# motion_detect.net
KiCad netlist of a schematic drawn in EAGLE
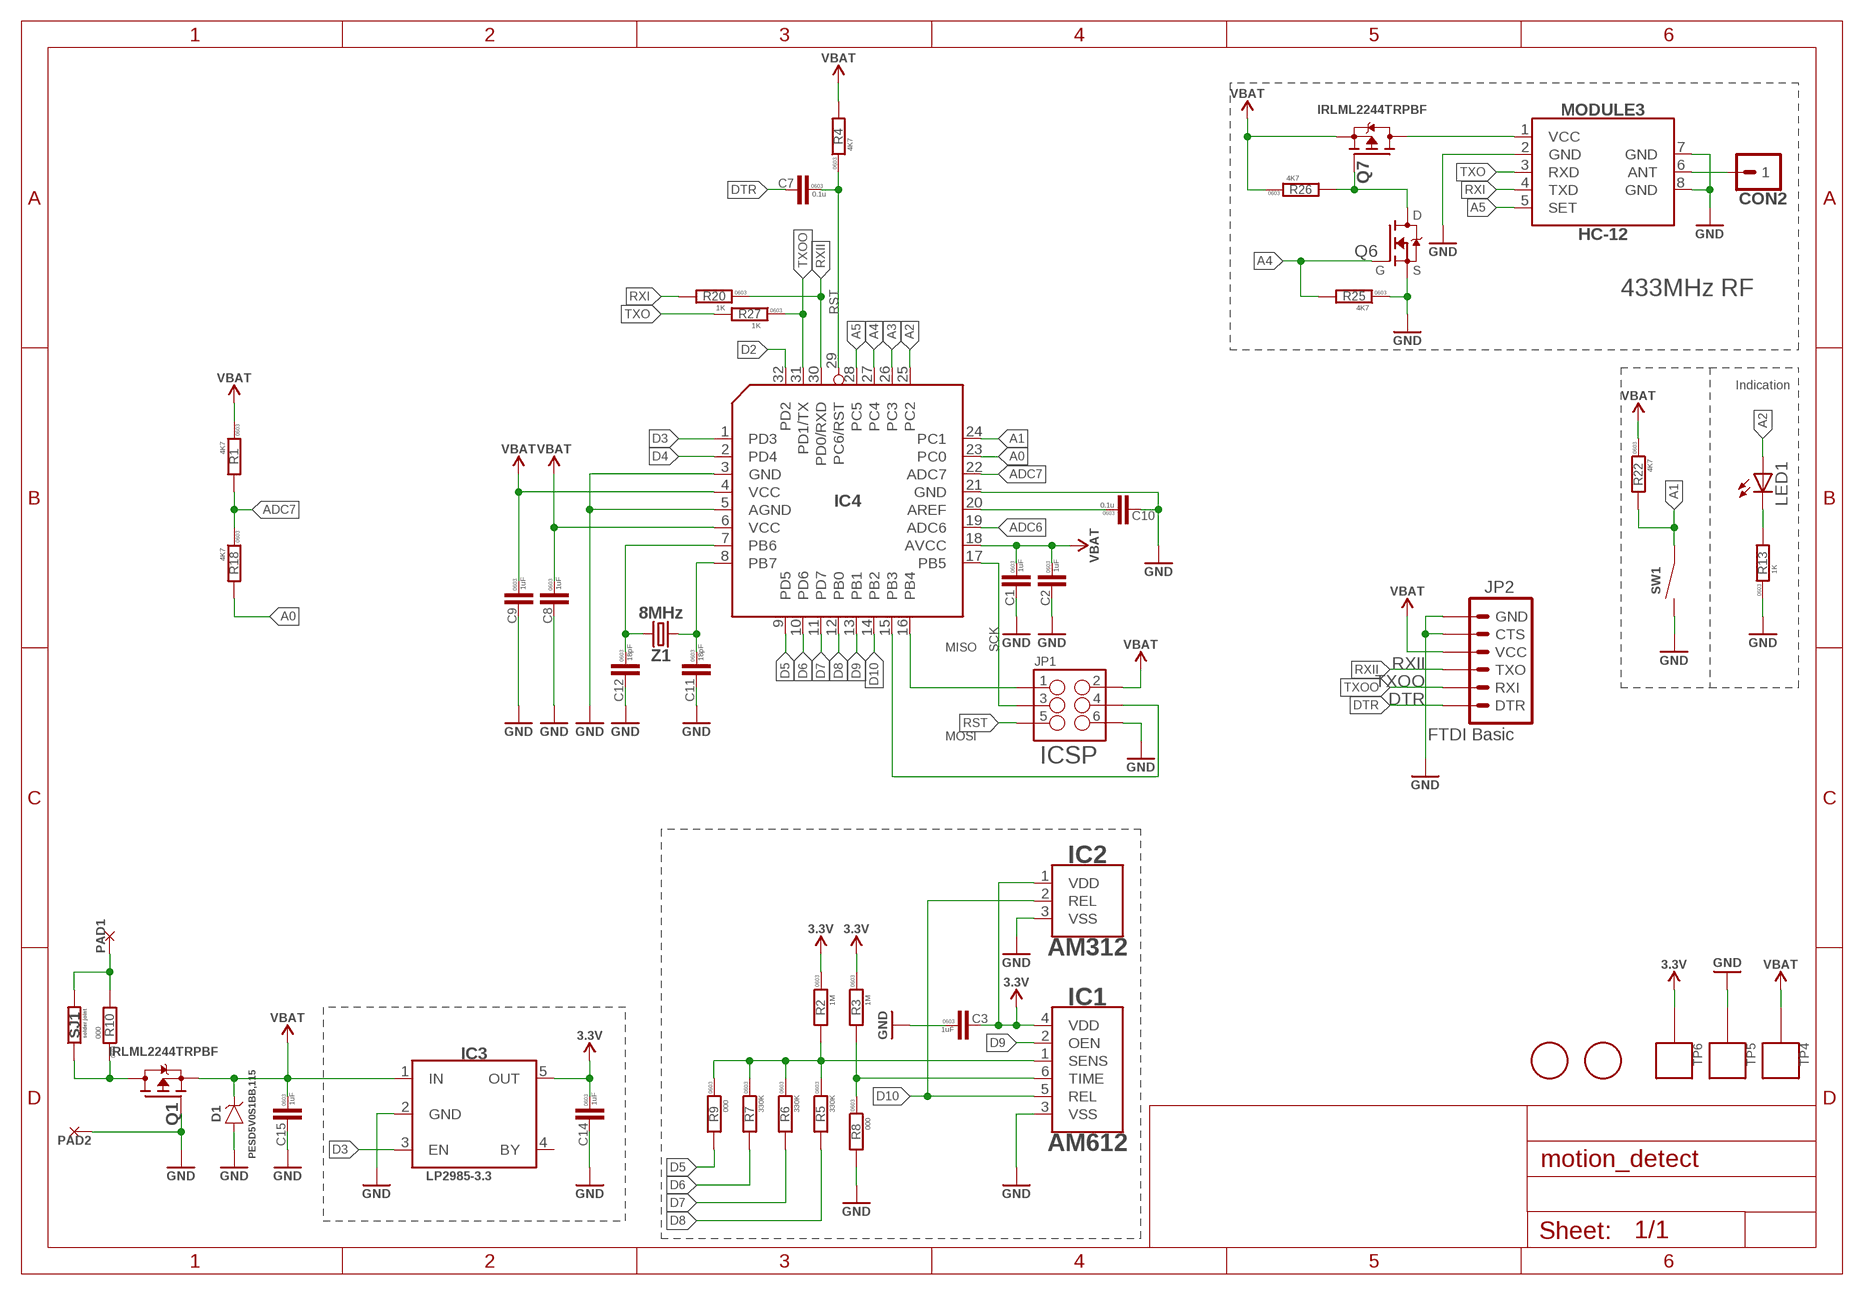
[diagram p0: schematic, sheet 1]

(export (version "E")
  (design (tool "Eeschema 10.0.6"))
  (components
    (comp (ref "C1")
      (value "1uF")
      (footprint "eagle-import:C0603")
      (libsource (lib "eagle-import") (part "C-0603"))
    )
    (comp (ref "C2")
      (value "1uF")
      (footprint "eagle-import:C0603")
      (libsource (lib "eagle-import") (part "C-0603"))
    )
    (comp (ref "C3")
      (value "1uF")
      (footprint "eagle-import:C0603")
      (libsource (lib "eagle-import") (part "C-0603"))
    )
    (comp (ref "C7")
      (value "0.1u")
      (footprint "eagle-import:C0603")
      (libsource (lib "eagle-import") (part "C-0603"))
    )
    (comp (ref "C8")
      (value "1uF")
      (footprint "eagle-import:C0603")
      (libsource (lib "eagle-import") (part "C-0603"))
    )
    (comp (ref "C9")
      (value "1uF")
      (footprint "eagle-import:C0603")
      (libsource (lib "eagle-import") (part "C-0603"))
    )
    (comp (ref "C10")
      (value "0.1u")
      (footprint "eagle-import:C0603")
      (libsource (lib "eagle-import") (part "C-0603"))
    )
    (comp (ref "C11")
      (value "18pF")
      (footprint "eagle-import:C0603")
      (libsource (lib "eagle-import") (part "C-0603"))
    )
    (comp (ref "C12")
      (value "18pF")
      (footprint "eagle-import:C0603")
      (libsource (lib "eagle-import") (part "C-0603"))
    )
    (comp (ref "C14")
      (value "1uF")
      (footprint "eagle-import:C0603")
      (libsource (lib "eagle-import") (part "C-0603"))
    )
    (comp (ref "C15")
      (value "1uF")
      (footprint "eagle-import:C0603")
      (libsource (lib "eagle-import") (part "C-0603"))
    )
    (comp (ref "CON2")
      (value "PINHEAD_1X01-2.54")
      (footprint "eagle-import:1X01-PTH-2.54")
      (libsource (lib "eagle-import") (part "PINHEAD_1X01-2.54"))
    )
    (comp (ref "D1")
      (value "PESD5V0S1BB,115")
      (footprint "eagle-import:SOD123")
      (fields (field (name "MANF") "Nexperia USA Inc"))
      (libsource (lib "eagle-import") (part "PESD5V0S1BB,115"))
    )
    (comp (ref "IC1")
      (value "AM612")
      (footprint "eagle-import:AM612")
      (libsource (lib "eagle-import") (part "AM612"))
    )
    (comp (ref "IC2")
      (value "AM312")
      (footprint "eagle-import:AM312_SIL")
      (libsource (lib "eagle-import") (part "AM312"))
    )
    (comp (ref "IC3")
      (value "3.3")
      (footprint "eagle-import:SOT23-5L")
      (fields (field (name "MANF") "Texas Instruments"))
      (libsource (lib "eagle-import") (part "LP2985-3.3V"))
    )
    (comp (ref "IC4")
      (value "ATMEGA168-TQFP32")
      (footprint "eagle-import:TQFP32-08")
      (fields (field (name "MANF#") "ATMEGA168"))
      (libsource (lib "eagle-import") (part "ATMEGA168-TQFP32"))
    )
    (comp (ref "JP1")
      (value "M03X2POGO_PINS")
      (footprint "eagle-import:2X3_POGO")
      (libsource (lib "eagle-import") (part "M03X2POGO_PINS"))
    )
    (comp (ref "JP2")
      (value "FTDI Basic")
      (footprint "eagle-import:1X06")
      (libsource (lib "eagle-import") (part "ARDUINO_SERIAL_PROGRAMPTH"))
    )
    (comp (ref "LED1")
      (value "LED-3MM")
      (footprint "eagle-import:LED-3MM")
      (libsource (lib "eagle-import") (part "LED-3MM"))
    )
    (comp (ref "MODULE3")
      (value "HC12")
      (footprint "eagle-import:HC-12")
      (libsource (lib "eagle-import") (part "HC12"))
    )
    (comp (ref "PAD1")
      (value "PAD-4X3")
      (footprint "eagle-import:4X3")
      (libsource (lib "eagle-import") (part "PAD-4X3"))
    )
    (comp (ref "PAD2")
      (value "PAD-4X3")
      (footprint "eagle-import:4X3")
      (libsource (lib "eagle-import") (part "PAD-4X3"))
    )
    (comp (ref "Q1")
      (value "IRLML2244TRPBF")
      (footprint "eagle-import:SOT23B-3")
      (fields (field (name "MANF#") "IRLML2244TRPBF") (field (name "MANF") "Infineon Technologies"))
      (libsource (lib "eagle-import") (part "IRLML2244TRPBF"))
    )
    (comp (ref "Q6")
      (value "IRLML2502-SOT23")
      (footprint "eagle-import:SOT23B-3")
      (fields (field (name "MANF") "Infineon Technologies"))
      (libsource (lib "eagle-import") (part "IRLML2502-SOT23"))
    )
    (comp (ref "Q7")
      (value "IRLML2244TRPBF")
      (footprint "eagle-import:SOT23B-3")
      (fields (field (name "MANF#") "IRLML2244TRPBF") (field (name "MANF") "Infineon Technologies"))
      (libsource (lib "eagle-import") (part "IRLML2244TRPBF"))
    )
    (comp (ref "R1")
      (value "4K7")
      (footprint "eagle-import:R0603")
      (libsource (lib "eagle-import") (part "R-0603"))
    )
    (comp (ref "R2")
      (value "1M")
      (footprint "eagle-import:R0603")
      (libsource (lib "eagle-import") (part "R-0603"))
    )
    (comp (ref "R3")
      (value "1M")
      (footprint "eagle-import:R0603")
      (libsource (lib "eagle-import") (part "R-0603"))
    )
    (comp (ref "R4")
      (value "4K7")
      (footprint "eagle-import:R0603")
      (libsource (lib "eagle-import") (part "R-0603"))
    )
    (comp (ref "R5")
      (value "330K")
      (footprint "eagle-import:R0603")
      (libsource (lib "eagle-import") (part "R-0603"))
    )
    (comp (ref "R6")
      (value "330K")
      (footprint "eagle-import:R0603")
      (libsource (lib "eagle-import") (part "R-0603"))
    )
    (comp (ref "R7")
      (value "330K")
      (footprint "eagle-import:R0603")
      (libsource (lib "eagle-import") (part "R-0603"))
    )
    (comp (ref "R8")
      (value "000")
      (footprint "eagle-import:R0603")
      (libsource (lib "eagle-import") (part "R-0603"))
    )
    (comp (ref "R9")
      (value "000")
      (footprint "eagle-import:R0603")
      (libsource (lib "eagle-import") (part "R-0603"))
    )
    (comp (ref "R10")
      (value "000")
      (footprint "eagle-import:R0603")
      (libsource (lib "eagle-import") (part "R-0603"))
    )
    (comp (ref "R13")
      (value "1K")
      (footprint "eagle-import:R0603")
      (libsource (lib "eagle-import") (part "R-0603"))
    )
    (comp (ref "R18")
      (value "4K7")
      (footprint "eagle-import:R0603")
      (libsource (lib "eagle-import") (part "R-0603"))
    )
    (comp (ref "R20")
      (value "1K")
      (footprint "eagle-import:R0603")
      (libsource (lib "eagle-import") (part "R-0603"))
    )
    (comp (ref "R22")
      (value "4K7")
      (footprint "eagle-import:R0603")
      (libsource (lib "eagle-import") (part "R-0603"))
    )
    (comp (ref "R25")
      (value "4K7")
      (footprint "eagle-import:R0603")
      (libsource (lib "eagle-import") (part "R-0603"))
    )
    (comp (ref "R26")
      (value "4K7")
      (footprint "eagle-import:R0603")
      (libsource (lib "eagle-import") (part "R-0603"))
    )
    (comp (ref "R27")
      (value "1K")
      (footprint "eagle-import:R0603")
      (libsource (lib "eagle-import") (part "R-0603"))
    )
    (comp (ref "SJ1")
      (value "SOLDER_JOINT_2P")
      (footprint "eagle-import:SJ_2P")
      (libsource (lib "eagle-import") (part "SOLDER_JOINT_2P"))
    )
    (comp (ref "SW1")
      (value "TACT_SWITCH-IT-1102S")
      (footprint "eagle-import:IT-1102S")
      (libsource (lib "eagle-import") (part "TACT_SWITCH-IT-1102S"))
    )
    (comp (ref "TP4")
      (value "PAD.05")
      (footprint "eagle-import:PAD.05X.05")
      (libsource (lib "eagle-import") (part "PAD.05"))
    )
    (comp (ref "TP5")
      (value "PAD.05")
      (footprint "eagle-import:PAD.05X.05")
      (libsource (lib "eagle-import") (part "PAD.05"))
    )
    (comp (ref "TP6")
      (value "PAD.05")
      (footprint "eagle-import:PAD.05X.05")
      (libsource (lib "eagle-import") (part "PAD.05"))
    )
    (comp (ref "U$4")
      (value "FIDUCIALMOUNT")
      (footprint "eagle-import:FIDUCIA-MOUNT")
      (libsource (lib "eagle-import") (part "FIDUCIALMOUNT"))
    )
    (comp (ref "U$6")
      (value "FIDUCIALMOUNT")
      (footprint "eagle-import:FIDUCIA-MOUNT")
      (libsource (lib "eagle-import") (part "FIDUCIALMOUNT"))
    )
    (comp (ref "Z1")
      (value "8MHz")
      (footprint "eagle-import:HC49UP")
      (fields (field (name "MANF") "Abracon LLC"))
      (libsource (lib "eagle-import") (part "CRYSTAL-8MHZHC49UP"))
    )
  )
  (nets
    (net (code "1") (name "/MISO") (class "Default")
      (node (ref "IC4") (pin "16") (pinfunction "PB4_16") (pintype "bidirectional"))
      (node (ref "JP1") (pin "P$1") (pinfunction "1_P$1") (pintype "bidirectional"))
    )
    (net (code "2") (name "/MOSI") (class "Default")
      (node (ref "IC4") (pin "15") (pinfunction "PB3_15") (pintype "bidirectional"))
      (node (ref "JP1") (pin "P$4") (pinfunction "4_P$4") (pintype "bidirectional"))
    )
    (net (code "3") (name "/SCK") (class "Default")
      (node (ref "IC4") (pin "17") (pinfunction "PB5_17") (pintype "bidirectional"))
      (node (ref "JP1") (pin "P$3") (pinfunction "3_P$3") (pintype "bidirectional"))
    )
    (net (code "4") (name "3.3V") (class "Default")
      (node (ref "C14") (pin "1") (pinfunction "1_1") (pintype "passive"))
      (node (ref "C3") (pin "2") (pinfunction "2_2") (pintype "passive"))
      (node (ref "IC1") (pin "4") (pinfunction "VDD_4") (pintype "bidirectional"))
      (node (ref "IC2") (pin "1") (pinfunction "VDD_1") (pintype "bidirectional"))
      (node (ref "IC3") (pin "5") (pinfunction "OUT_5") (pintype "bidirectional"))
      (node (ref "R2") (pin "1") (pinfunction "1_1") (pintype "passive"))
      (node (ref "R3") (pin "1") (pinfunction "1_1") (pintype "passive"))
      (node (ref "TP6") (pin "P$1") (pinfunction "P$1_P$1") (pintype "passive"))
    )
    (net (code "5") (name "A0") (class "Default")
      (node (ref "IC4") (pin "23") (pinfunction "PC0_23") (pintype "bidirectional"))
      (node (ref "R18") (pin "2") (pinfunction "2_2") (pintype "passive"))
    )
    (net (code "6") (name "A1") (class "Default")
      (node (ref "IC4") (pin "24") (pinfunction "PC1_24") (pintype "bidirectional"))
      (node (ref "R22") (pin "2") (pinfunction "2_2") (pintype "passive"))
      (node (ref "SW1") (pin "1") (pinfunction "1_1") (pintype "bidirectional"))
      (node (ref "SW1") (pin "2") (pinfunction "1_2") (pintype "bidirectional"))
    )
    (net (code "7") (name "A2") (class "Default")
      (node (ref "IC4") (pin "25") (pinfunction "PC2_25") (pintype "bidirectional"))
      (node (ref "LED1") (pin "A") (pinfunction "A_A") (pintype "passive"))
    )
    (net (code "8") (name "A3") (class "Default")
      (node (ref "IC4") (pin "26") (pinfunction "PC3_26") (pintype "bidirectional"))
    )
    (net (code "9") (name "A4") (class "Default")
      (node (ref "IC4") (pin "27") (pinfunction "PC4_27") (pintype "bidirectional"))
      (node (ref "Q6") (pin "1") (pinfunction "G_1") (pintype "passive"))
      (node (ref "R25") (pin "2") (pinfunction "2_2") (pintype "passive"))
    )
    (net (code "10") (name "A5") (class "Default")
      (node (ref "IC4") (pin "28") (pinfunction "PC5_28") (pintype "bidirectional"))
      (node (ref "MODULE3") (pin "5") (pinfunction "SET_5") (pintype "input"))
    )
    (net (code "11") (name "ADC6") (class "Default")
      (node (ref "IC4") (pin "19") (pinfunction "ADC6_19") (pintype "bidirectional"))
    )
    (net (code "12") (name "ADC7") (class "Default")
      (node (ref "IC4") (pin "22") (pinfunction "ADC7_22") (pintype "bidirectional"))
      (node (ref "R1") (pin "2") (pinfunction "2_2") (pintype "passive"))
      (node (ref "R18") (pin "1") (pinfunction "1_1") (pintype "passive"))
    )
    (net (code "13") (name "D2") (class "Default")
      (node (ref "IC4") (pin "32") (pinfunction "PD2_32") (pintype "bidirectional"))
    )
    (net (code "14") (name "D3") (class "Default")
      (node (ref "IC3") (pin "3") (pinfunction "EN_3") (pintype "bidirectional"))
      (node (ref "IC4") (pin "1") (pinfunction "PD3_1") (pintype "bidirectional"))
    )
    (net (code "15") (name "D4") (class "Default")
      (node (ref "IC4") (pin "2") (pinfunction "PD4_2") (pintype "bidirectional"))
    )
    (net (code "16") (name "D5") (class "Default")
      (node (ref "IC4") (pin "9") (pinfunction "PD5_9") (pintype "bidirectional"))
      (node (ref "R9") (pin "2") (pinfunction "2_2") (pintype "passive"))
    )
    (net (code "17") (name "D6") (class "Default")
      (node (ref "IC4") (pin "10") (pinfunction "PD6_10") (pintype "bidirectional"))
      (node (ref "R7") (pin "2") (pinfunction "2_2") (pintype "passive"))
    )
    (net (code "18") (name "D7") (class "Default")
      (node (ref "IC4") (pin "11") (pinfunction "PD7_11") (pintype "bidirectional"))
      (node (ref "R6") (pin "2") (pinfunction "2_2") (pintype "passive"))
    )
    (net (code "19") (name "D8") (class "Default")
      (node (ref "IC4") (pin "12") (pinfunction "PB0_12") (pintype "bidirectional"))
      (node (ref "R5") (pin "2") (pinfunction "2_2") (pintype "passive"))
    )
    (net (code "20") (name "D9") (class "Default")
      (node (ref "IC1") (pin "2") (pinfunction "OEN_2") (pintype "bidirectional"))
      (node (ref "IC4") (pin "13") (pinfunction "PB1_13") (pintype "bidirectional"))
    )
    (net (code "21") (name "D10") (class "Default")
      (node (ref "IC1") (pin "5") (pinfunction "REL_5") (pintype "bidirectional"))
      (node (ref "IC2") (pin "2") (pinfunction "REL_2") (pintype "bidirectional"))
      (node (ref "IC4") (pin "14") (pinfunction "PB2_14") (pintype "bidirectional"))
    )
    (net (code "22") (name "DTR") (class "Default")
      (node (ref "C7") (pin "2") (pinfunction "2_2") (pintype "passive"))
      (node (ref "JP2") (pin "1") (pinfunction "DTR_1") (pintype "passive"))
    )
    (net (code "23") (name "GND") (class "Default")
      (node (ref "C1") (pin "2") (pinfunction "2_2") (pintype "passive"))
      (node (ref "C10") (pin "2") (pinfunction "2_2") (pintype "passive"))
      (node (ref "C11") (pin "2") (pinfunction "2_2") (pintype "passive"))
      (node (ref "C12") (pin "2") (pinfunction "2_2") (pintype "passive"))
      (node (ref "C14") (pin "2") (pinfunction "2_2") (pintype "passive"))
      (node (ref "C15") (pin "2") (pinfunction "2_2") (pintype "passive"))
      (node (ref "C2") (pin "2") (pinfunction "2_2") (pintype "passive"))
      (node (ref "C3") (pin "1") (pinfunction "1_1") (pintype "passive"))
      (node (ref "C8") (pin "2") (pinfunction "2_2") (pintype "passive"))
      (node (ref "C9") (pin "2") (pinfunction "2_2") (pintype "passive"))
      (node (ref "D1") (pin "A") (pinfunction "A_A") (pintype "passive"))
      (node (ref "IC1") (pin "3") (pinfunction "VSS_3") (pintype "bidirectional"))
      (node (ref "IC2") (pin "3") (pinfunction "VSS_3") (pintype "bidirectional"))
      (node (ref "IC3") (pin "2") (pinfunction "GND_2") (pintype "bidirectional"))
      (node (ref "IC4") (pin "21") (pinfunction "GND_21") (pintype "bidirectional"))
      (node (ref "IC4") (pin "3") (pinfunction "GND_3") (pintype "bidirectional"))
      (node (ref "IC4") (pin "5") (pinfunction "AGND_5") (pintype "bidirectional"))
      (node (ref "JP1") (pin "P$6") (pinfunction "6_P$6") (pintype "bidirectional"))
      (node (ref "JP2") (pin "5") (pinfunction "CTS_5") (pintype "passive"))
      (node (ref "JP2") (pin "6") (pinfunction "GND_6") (pintype "passive"))
      (node (ref "MODULE3") (pin "2") (pinfunction "GND_2") (pintype "power_in"))
      (node (ref "MODULE3") (pin "7") (pinfunction "GND_7") (pintype "power_in"))
      (node (ref "MODULE3") (pin "8") (pinfunction "GND_8") (pintype "power_in"))
      (node (ref "PAD2") (pin "P$1") (pinfunction "P$1_P$1") (pintype "bidirectional"))
      (node (ref "Q1") (pin "1") (pinfunction "G_1") (pintype "passive"))
      (node (ref "Q6") (pin "2") (pinfunction "S_2") (pintype "passive"))
      (node (ref "R13") (pin "1") (pinfunction "1_1") (pintype "passive"))
      (node (ref "R25") (pin "1") (pinfunction "1_1") (pintype "passive"))
      (node (ref "R8") (pin "2") (pinfunction "2_2") (pintype "passive"))
      (node (ref "SW1") (pin "3") (pinfunction "2_3") (pintype "bidirectional"))
      (node (ref "SW1") (pin "4") (pinfunction "2_4") (pintype "bidirectional"))
      (node (ref "TP5") (pin "P$1") (pinfunction "P$1_P$1") (pintype "passive"))
    )
    (net (code "24") (name "Net-(IC1-SENS)") (class "Default")
      (node (ref "IC1") (pin "1") (pinfunction "SENS_1") (pintype "bidirectional"))
      (node (ref "R2") (pin "2") (pinfunction "2_2") (pintype "passive"))
      (node (ref "R5") (pin "1") (pinfunction "1_1") (pintype "passive"))
      (node (ref "R6") (pin "1") (pinfunction "1_1") (pintype "passive"))
      (node (ref "R7") (pin "1") (pinfunction "1_1") (pintype "passive"))
      (node (ref "R9") (pin "1") (pinfunction "1_1") (pintype "passive"))
    )
    (net (code "25") (name "Net-(IC1-TIME)") (class "Default")
      (node (ref "IC1") (pin "6") (pinfunction "TIME_6") (pintype "bidirectional"))
      (node (ref "R3") (pin "2") (pinfunction "2_2") (pintype "passive"))
      (node (ref "R8") (pin "1") (pinfunction "1_1") (pintype "passive"))
    )
    (net (code "26") (name "Net-(IC4-AREF)") (class "Default")
      (node (ref "C10") (pin "1") (pinfunction "1_1") (pintype "passive"))
      (node (ref "IC4") (pin "20") (pinfunction "AREF_20") (pintype "bidirectional"))
    )
    (net (code "27") (name "Net-(IC4-PB6)") (class "Default")
      (node (ref "C12") (pin "1") (pinfunction "1_1") (pintype "passive"))
      (node (ref "IC4") (pin "7") (pinfunction "PB6_7") (pintype "bidirectional"))
      (node (ref "Z1") (pin "2") (pinfunction "2_2") (pintype "passive"))
    )
    (net (code "28") (name "Net-(IC4-PB7)") (class "Default")
      (node (ref "C11") (pin "1") (pinfunction "1_1") (pintype "passive"))
      (node (ref "IC4") (pin "8") (pinfunction "PB7_8") (pintype "bidirectional"))
      (node (ref "Z1") (pin "1") (pinfunction "1_1") (pintype "passive"))
    )
    (net (code "29") (name "Net-(LED1-C)") (class "Default")
      (node (ref "LED1") (pin "K") (pinfunction "C_K") (pintype "passive"))
      (node (ref "R13") (pin "2") (pinfunction "2_2") (pintype "passive"))
    )
    (net (code "30") (name "Net-(MODULE3-ANT)") (class "Default")
      (node (ref "CON2") (pin "1") (pinfunction "1_1") (pintype "passive"))
      (node (ref "MODULE3") (pin "6") (pinfunction "ANT_6") (pintype "bidirectional"))
    )
    (net (code "31") (name "Net-(MODULE3-VCC)") (class "Default")
      (node (ref "MODULE3") (pin "1") (pinfunction "VCC_1") (pintype "bidirectional"))
      (node (ref "Q7") (pin "3") (pinfunction "D_3") (pintype "passive"))
    )
    (net (code "32") (name "Net-(PAD1-PadP$1)") (class "Default")
      (node (ref "PAD1") (pin "P$1") (pinfunction "P$1_P$1") (pintype "bidirectional"))
      (node (ref "R10") (pin "2") (pinfunction "2_2") (pintype "passive"))
      (node (ref "SJ1") (pin "2") (pinfunction "2_2") (pintype "passive"))
    )
    (net (code "33") (name "Net-(Q1-D)") (class "Default")
      (node (ref "Q1") (pin "3") (pinfunction "D_3") (pintype "passive"))
      (node (ref "R10") (pin "1") (pinfunction "1_1") (pintype "passive"))
      (node (ref "SJ1") (pin "1") (pinfunction "1_1") (pintype "passive"))
    )
    (net (code "34") (name "Net-(Q6-D)") (class "Default")
      (node (ref "Q6") (pin "3") (pinfunction "D_3") (pintype "passive"))
      (node (ref "Q7") (pin "1") (pinfunction "G_1") (pintype "passive"))
      (node (ref "R26") (pin "2") (pinfunction "2_2") (pintype "passive"))
    )
    (net (code "35") (name "RST") (class "Default")
      (node (ref "C7") (pin "1") (pinfunction "1_1") (pintype "passive"))
      (node (ref "IC4") (pin "29") (pinfunction "PC6/RST_29") (pintype "bidirectional"))
      (node (ref "JP1") (pin "P$5") (pinfunction "5_P$5") (pintype "bidirectional"))
      (node (ref "R4") (pin "1") (pinfunction "1_1") (pintype "passive"))
    )
    (net (code "36") (name "RXI") (class "Default")
      (node (ref "MODULE3") (pin "4") (pinfunction "TXD_4") (pintype "output"))
      (node (ref "R20") (pin "2") (pinfunction "2_2") (pintype "passive"))
    )
    (net (code "37") (name "RXII") (class "Default")
      (node (ref "IC4") (pin "30") (pinfunction "PD0/RXD_30") (pintype "bidirectional"))
      (node (ref "JP2") (pin "3") (pinfunction "TXO_3") (pintype "passive"))
      (node (ref "R20") (pin "1") (pinfunction "1_1") (pintype "passive"))
    )
    (net (code "38") (name "TXO") (class "Default")
      (node (ref "MODULE3") (pin "3") (pinfunction "RXD_3") (pintype "input"))
      (node (ref "R27") (pin "2") (pinfunction "2_2") (pintype "passive"))
    )
    (net (code "39") (name "TXOO") (class "Default")
      (node (ref "IC4") (pin "31") (pinfunction "PD1/TX_31") (pintype "bidirectional"))
      (node (ref "JP2") (pin "2") (pinfunction "RXI_2") (pintype "passive"))
      (node (ref "R27") (pin "1") (pinfunction "1_1") (pintype "passive"))
    )
    (net (code "40") (name "VBAT") (class "Default")
      (node (ref "C1") (pin "1") (pinfunction "1_1") (pintype "passive"))
      (node (ref "C15") (pin "1") (pinfunction "1_1") (pintype "passive"))
      (node (ref "C2") (pin "1") (pinfunction "1_1") (pintype "passive"))
      (node (ref "C8") (pin "1") (pinfunction "1_1") (pintype "passive"))
      (node (ref "C9") (pin "1") (pinfunction "1_1") (pintype "passive"))
      (node (ref "D1") (pin "C") (pinfunction "C_C") (pintype "passive"))
      (node (ref "IC3") (pin "1") (pinfunction "IN_1") (pintype "bidirectional"))
      (node (ref "IC4") (pin "18") (pinfunction "AVCC_18") (pintype "bidirectional"))
      (node (ref "IC4") (pin "4") (pinfunction "VCC_4") (pintype "bidirectional"))
      (node (ref "IC4") (pin "6") (pinfunction "VCC_6") (pintype "bidirectional"))
      (node (ref "JP1") (pin "P$2") (pinfunction "2_P$2") (pintype "bidirectional"))
      (node (ref "JP2") (pin "4") (pinfunction "VCC_4") (pintype "passive"))
      (node (ref "Q1") (pin "2") (pinfunction "S_2") (pintype "passive"))
      (node (ref "Q7") (pin "2") (pinfunction "S_2") (pintype "passive"))
      (node (ref "R1") (pin "1") (pinfunction "1_1") (pintype "passive"))
      (node (ref "R22") (pin "1") (pinfunction "1_1") (pintype "passive"))
      (node (ref "R26") (pin "1") (pinfunction "1_1") (pintype "passive"))
      (node (ref "R4") (pin "2") (pinfunction "2_2") (pintype "passive"))
      (node (ref "TP4") (pin "P$1") (pinfunction "P$1_P$1") (pintype "passive"))
    )
    (net (code "41") (name "unconnected-(IC3-BY-Pad4)") (class "Default")
      (node (ref "IC3") (pin "4") (pinfunction "BY_4") (pintype "bidirectional"))
    )
  )
)
